# 01_Power_Suppy.net
KiCad netlist of a schematic drawn in Altium Designer
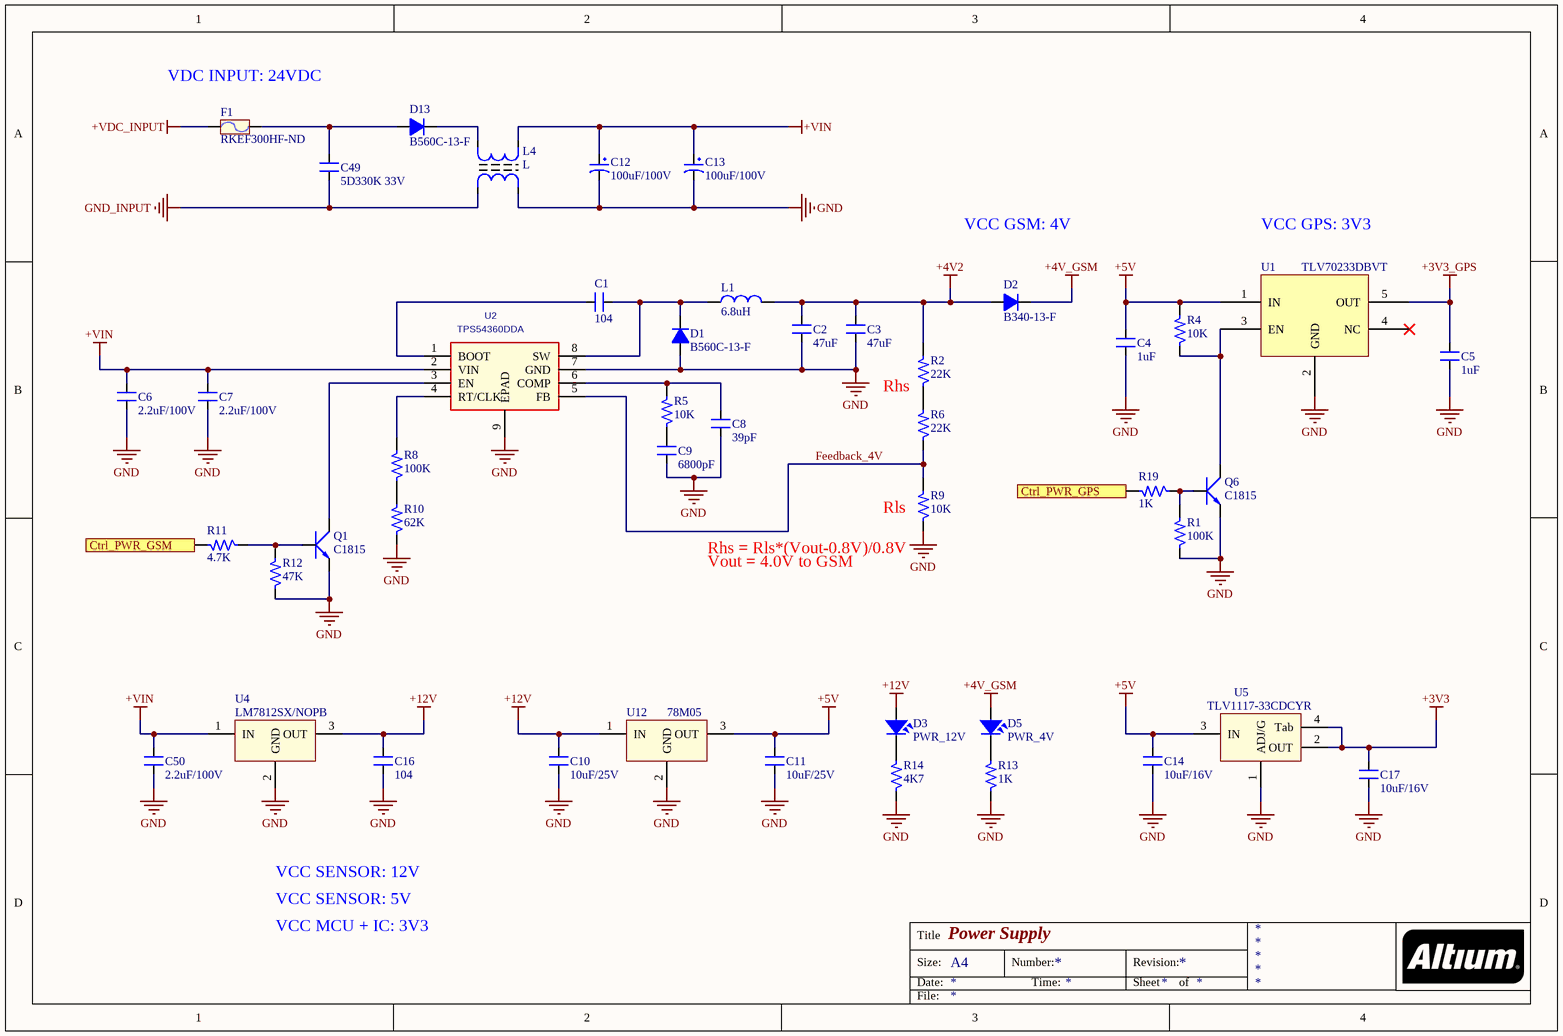
[diagram p0: [01] Power Suppy.SchDoc]

(export (version "E")
  (design (tool "Eeschema 10.0.6"))
  (components
    (comp (ref "C1")
      (value "104")
      (footprint "C0603 SMT")
      (description "Cap SMD")
      (libsource (lib "GPS_Traking_V1_1") (part "CM"))
    )
    (comp (ref "C2")
      (value "47uF")
      (footprint "SM-1210")
      (description "CAP CER 47UF 10V X5R 1210")
      (libsource (lib "GPS_Traking_V1_1") (part "CM"))
    )
    (comp (ref "C3")
      (value "47uF")
      (footprint "SM-1210")
      (description "CAP CER 47UF 10V X5R 1210 1276-3380-2-ND")
      (libsource (lib "GPS_Traking_V1_1") (part "CM"))
    )
    (comp (ref "C4")
      (value "1uF")
      (footprint "C0603 SMT")
      (description "Cap SMD")
      (libsource (lib "GPS_Traking_V1_1") (part "CM"))
    )
    (comp (ref "C5")
      (value "1uF")
      (footprint "C0603 SMT")
      (description "Cap SMD")
      (libsource (lib "GPS_Traking_V1_1") (part "CM"))
    )
    (comp (ref "C6")
      (value "2.2uF/100V")
      (footprint "SM-1210")
      (description "CAP CER 2.2UF 100V X7R 1210  445-4498-2-ND")
      (libsource (lib "GPS_Traking_V1_1") (part "CM"))
    )
    (comp (ref "C7")
      (value "2.2uF/100V")
      (footprint "SM-1210")
      (description "CAP CER 2.2UF 100V X7R 1210  445-4498-2-ND")
      (libsource (lib "GPS_Traking_V1_1") (part "CM"))
    )
    (comp (ref "C8")
      (value "39pF")
      (footprint "C0603 SMT")
      (description "Cap SMD")
      (libsource (lib "GPS_Traking_V1_1") (part "CM"))
    )
    (comp (ref "C9")
      (value "6800pF")
      (footprint "C0603 SMT")
      (description "Cap SMD")
      (libsource (lib "GPS_Traking_V1_1") (part "CM"))
    )
    (comp (ref "C10")
      (value "10uF/25V")
      (footprint "C0603 SMT")
      (description "Cap SMD")
      (libsource (lib "GPS_Traking_V1_1") (part "CM"))
    )
    (comp (ref "C11")
      (value "10uF/25V")
      (footprint "C0603 SMT")
      (description "Cap SMD")
      (libsource (lib "GPS_Traking_V1_1") (part "CM"))
    )
    (comp (ref "C12")
      (value "100uF/100V")
      (footprint "CP1.5/3.4")
      (description "Cap 1000uF/16V - 220uF/50V")
      (libsource (lib "GPS_Traking_V1_1") (part "CP4"))
    )
    (comp (ref "C13")
      (value "100uF/100V")
      (footprint "CP1.5/3.4")
      (description "Cap 1000uF/16V - 220uF/50V")
      (libsource (lib "GPS_Traking_V1_1") (part "CP4"))
    )
    (comp (ref "C14")
      (value "10uF/16V")
      (footprint "C0603 SMT")
      (description "Cap SMD")
      (libsource (lib "GPS_Traking_V1_1") (part "CM"))
    )
    (comp (ref "C16")
      (value "104")
      (footprint "C0603 SMT")
      (description "Cap SMD")
      (libsource (lib "GPS_Traking_V1_1") (part "CM"))
    )
    (comp (ref "C17")
      (value "10uF/16V")
      (footprint "C0603 SMT")
      (description "Cap SMD")
      (libsource (lib "GPS_Traking_V1_1") (part "CM"))
    )
    (comp (ref "C49")
      (value "5D330K 33V")
      (footprint "CN2")
      (fields (field (name "DESIGNED BY") "VanDungEvn"))
      (libsource (lib "khapham") (part "CN"))
    )
    (comp (ref "C50")
      (value "2.2uF/100V")
      (footprint "SM-1210")
      (description "CAP CER 2.2UF 100V X7R 1210  445-4498-2-ND")
      (libsource (lib "GPS_Traking_V1_1") (part "CM"))
    )
    (comp (ref "D1")
      (value "B560C-13-F")
      (footprint "DO-214AB SMC")
      (description "DIODE SCHOTTKY 60V 5A SMC")
      (libsource (lib "GPS_Traking_V1_1") (part "D5A"))
    )
    (comp (ref "D2")
      (value "B340-13-F")
      (footprint "DO-214AB SMA")
      (description "DIODE SCHOTTKY 40V 3A SMC")
      (libsource (lib "GPS_Traking_V1_1") (part "D1A"))
    )
    (comp (ref "D3")
      (value "PWR_12V")
      (footprint "Led_0603_Yellow")
      (description "LED Single colour Green and Red")
      (libsource (lib "GPS_Traking_V1_1") (part "LED"))
    )
    (comp (ref "D5")
      (value "PWR_4V")
      (footprint "Led_0603_Green")
      (description "LED Single colour Green and Red")
      (libsource (lib "GPS_Traking_V1_1") (part "LED"))
    )
    (comp (ref "D13")
      (value "B560C-13-F")
      (footprint "DO-214AB SMC")
      (description "DIODE SCHOTTKY 60V 5A SMC")
      (libsource (lib "GPS_Traking_V1_1") (part "D5A"))
    )
    (comp (ref "F1")
      (value "RKEF300HF-ND")
      (footprint "FUSE2")
      (description "PTC RESET FUSE 60V 3A RADIAL")
      (fields (field (name "DESIGNED BY") "VanDungEvn"))
      (libsource (lib "khapham") (part "Fuse"))
    )
    (comp (ref "L1")
      (value "6.8uH")
      (footprint "L01 SMD 12*12*6")
      (description "FIXED IND 6.2UH 5.7A 22.4 MOHM")
      (libsource (lib "GPS_Traking_V1_1") (part "L1"))
    )
    (comp (ref "L4")
      (value "L")
      (footprint "L2 UF9.8")
      (description "Inductor")
      (fields (field (name "DESIGNED BY") "VanDungEvn"))
      (libsource (lib "GPS_Traking_V1_1") (part "L2x220"))
    )
    (comp (ref "Q1")
      (value "C1815")
      (footprint "SOT23B")
      (description "NPN 600mW, ECB")
      (libsource (lib "GPS_Traking_V1_1") (part "C1815"))
    )
    (comp (ref "Q6")
      (value "C1815")
      (footprint "SOT23B")
      (description "NPN 600mW, ECB")
      (libsource (lib "GPS_Traking_V1_1") (part "C1815"))
    )
    (comp (ref "R1")
      (value "100K")
      (footprint "R0603 -SMT")
      (description "Resistor SMD")
      (libsource (lib "GPS_Traking_V1_1") (part "RM"))
    )
    (comp (ref "R2")
      (value "22K")
      (footprint "R0603 -SMT")
      (description "Resistor SMD")
      (libsource (lib "GPS_Traking_V1_1") (part "RM"))
    )
    (comp (ref "R4")
      (value "10K")
      (footprint "R0603 -SMT")
      (description "Resistor SMD")
      (libsource (lib "GPS_Traking_V1_1") (part "RM"))
    )
    (comp (ref "R5")
      (value "10K")
      (footprint "R0603 -SMT")
      (description "Resistor SMD")
      (libsource (lib "GPS_Traking_V1_1") (part "RM"))
    )
    (comp (ref "R6")
      (value "22K")
      (footprint "R0603 -SMT")
      (description "Resistor SMD")
      (libsource (lib "GPS_Traking_V1_1") (part "RM"))
    )
    (comp (ref "R8")
      (value "100K")
      (footprint "R0603 -SMT")
      (description "Resistor SMD")
      (libsource (lib "GPS_Traking_V1_1") (part "RM"))
    )
    (comp (ref "R9")
      (value "10K")
      (footprint "R0603 -SMT")
      (description "Resistor SMD")
      (libsource (lib "GPS_Traking_V1_1") (part "RM"))
    )
    (comp (ref "R10")
      (value "62K")
      (footprint "R0603 -SMT")
      (description "Resistor SMD")
      (libsource (lib "GPS_Traking_V1_1") (part "RM"))
    )
    (comp (ref "R11")
      (value "4.7K")
      (footprint "R0603 -SMT")
      (description "Resistor SMD")
      (libsource (lib "GPS_Traking_V1_1") (part "RM"))
    )
    (comp (ref "R12")
      (value "47K")
      (footprint "R0603 -SMT")
      (description "Resistor SMD")
      (libsource (lib "GPS_Traking_V1_1") (part "RM"))
    )
    (comp (ref "R13")
      (value "1K")
      (footprint "R0603 -SMT")
      (description "Resistor SMD")
      (libsource (lib "GPS_Traking_V1_1") (part "RM"))
    )
    (comp (ref "R14")
      (value "4K7")
      (footprint "R0603 -SMT")
      (description "Resistor SMD")
      (libsource (lib "GPS_Traking_V1_1") (part "RM"))
    )
    (comp (ref "R19")
      (value "1K")
      (footprint "R0603 -SMT")
      (description "Resistor SMD")
      (libsource (lib "GPS_Traking_V1_1") (part "RM"))
    )
    (comp (ref "U1")
      (value "TLV70233DBVT")
      (footprint "TLV70233_3.3V")
      (libsource (lib "GPS_Traking_V1_1") (part "TLV70233_3.3V"))
    )
    (comp (ref "U2")
      (value "TPS54360DDA")
      (footprint "DDA8_3P1X2P4-M")
      (description "REG BUCK SPLIT RAIL 8SOPWRPAD")
      (libsource (lib "GPS_Traking_V1_1") (part "TPS54360DDA"))
    )
    (comp (ref "U4")
      (value "LM7812SX/NOPB")
      (footprint "TO-263-4")
      (libsource (lib "GPS_Traking_V1_1") (part "LM78xx"))
    )
    (comp (ref "U5")
      (value "TLV1117-33CDCYR")
      (footprint "SOT223-4N")
      (description "3v3")
      (libsource (lib "GPS_Traking_V1_1") (part "LM1117"))
    )
    (comp (ref "U12")
      (value "78M05")
      (footprint "TO252-3L")
      (description "On ap +, from + 5 to + 24VDC")
      (libsource (lib "GPS_Traking_V1_1") (part "LM78xx"))
    )
  )
  (nets
    (net (code "1") (name "+3V3") (class "Default")
      (node (ref "C17") (pin "2") (pinfunction "2_2") (pintype "passive"))
      (node (ref "U5") (pin "2") (pinfunction "OUT_2") (pintype "passive"))
      (node (ref "U5") (pin "4") (pinfunction "Tab_4") (pintype "passive"))
    )
    (net (code "2") (name "+3V3_GPS") (class "Default")
      (node (ref "C5") (pin "2") (pinfunction "2_2") (pintype "passive"))
      (node (ref "U1") (pin "5") (pinfunction "OUT_5") (pintype "passive"))
    )
    (net (code "3") (name "+4V2") (class "Default")
      (node (ref "C2") (pin "2") (pinfunction "2_2") (pintype "passive"))
      (node (ref "C3") (pin "2") (pinfunction "2_2") (pintype "passive"))
      (node (ref "D2") (pin "1") (pinfunction "A_1") (pintype "passive"))
      (node (ref "L1") (pin "2") (pinfunction "2_2") (pintype "passive"))
      (node (ref "R2") (pin "2") (pinfunction "2_2") (pintype "passive"))
    )
    (net (code "4") (name "+4V_GSM") (class "Default")
      (node (ref "D2") (pin "2") (pinfunction "K_2") (pintype "passive"))
      (node (ref "D5") (pin "1") (pinfunction "1_1") (pintype "passive"))
    )
    (net (code "5") (name "+5V") (class "Default")
      (node (ref "C11") (pin "2") (pinfunction "2_2") (pintype "passive"))
      (node (ref "C14") (pin "2") (pinfunction "2_2") (pintype "passive"))
      (node (ref "C4") (pin "2") (pinfunction "2_2") (pintype "passive"))
      (node (ref "R4") (pin "2") (pinfunction "2_2") (pintype "passive"))
      (node (ref "U1") (pin "1") (pinfunction "IN_1") (pintype "passive"))
      (node (ref "U12") (pin "3") (pinfunction "OUT_3") (pintype "passive"))
      (node (ref "U5") (pin "3") (pinfunction "IN_3") (pintype "passive"))
    )
    (net (code "6") (name "+12V") (class "Default")
      (node (ref "C10") (pin "2") (pinfunction "2_2") (pintype "passive"))
      (node (ref "C16") (pin "2") (pinfunction "2_2") (pintype "passive"))
      (node (ref "D3") (pin "1") (pinfunction "1_1") (pintype "passive"))
      (node (ref "U12") (pin "1") (pinfunction "IN_1") (pintype "passive"))
      (node (ref "U4") (pin "3") (pinfunction "OUT_3") (pintype "passive"))
    )
    (net (code "7") (name "+VDC_INPUT") (class "Default")
      (node (ref "F1") (pin "1") (pinfunction "1_1") (pintype "passive"))
    )
    (net (code "8") (name "+VIN") (class "Default")
      (node (ref "C12") (pin "1") (pinfunction "1_1") (pintype "passive"))
      (node (ref "C13") (pin "1") (pinfunction "1_1") (pintype "passive"))
      (node (ref "C50") (pin "2") (pinfunction "2_2") (pintype "passive"))
      (node (ref "C6") (pin "2") (pinfunction "2_2") (pintype "passive"))
      (node (ref "C7") (pin "2") (pinfunction "2_2") (pintype "passive"))
      (node (ref "L4") (pin "3") (pinfunction "3_3") (pintype "passive"))
      (node (ref "U2") (pin "2") (pinfunction "VIN_2") (pintype "passive"))
      (node (ref "U4") (pin "1") (pinfunction "IN_1") (pintype "passive"))
    )
    (net (code "9") (name "/Ctrl_PWR_GPS") (class "Default")
      (node (ref "R19") (pin "2") (pinfunction "2_2") (pintype "passive"))
    )
    (net (code "10") (name "/Ctrl_PWR_GSM") (class "Default")
      (node (ref "R11") (pin "2") (pinfunction "2_2") (pintype "passive"))
    )
    (net (code "11") (name "/Feedback_4V") (class "Default")
      (node (ref "R6") (pin "1") (pinfunction "1_1") (pintype "passive"))
      (node (ref "R9") (pin "2") (pinfunction "2_2") (pintype "passive"))
      (node (ref "U2") (pin "5") (pinfunction "FB_5") (pintype "passive"))
    )
    (net (code "12") (name "GND") (class "Default")
      (node (ref "C10") (pin "1") (pinfunction "1_1") (pintype "passive"))
      (node (ref "C11") (pin "1") (pinfunction "1_1") (pintype "passive"))
      (node (ref "C12") (pin "2") (pinfunction "2_2") (pintype "passive"))
      (node (ref "C13") (pin "2") (pinfunction "2_2") (pintype "passive"))
      (node (ref "C14") (pin "1") (pinfunction "1_1") (pintype "passive"))
      (node (ref "C16") (pin "1") (pinfunction "1_1") (pintype "passive"))
      (node (ref "C17") (pin "1") (pinfunction "1_1") (pintype "passive"))
      (node (ref "C2") (pin "1") (pinfunction "1_1") (pintype "passive"))
      (node (ref "C3") (pin "1") (pinfunction "1_1") (pintype "passive"))
      (node (ref "C4") (pin "1") (pinfunction "1_1") (pintype "passive"))
      (node (ref "C5") (pin "1") (pinfunction "1_1") (pintype "passive"))
      (node (ref "C50") (pin "1") (pinfunction "1_1") (pintype "passive"))
      (node (ref "C6") (pin "1") (pinfunction "1_1") (pintype "passive"))
      (node (ref "C7") (pin "1") (pinfunction "1_1") (pintype "passive"))
      (node (ref "C8") (pin "1") (pinfunction "1_1") (pintype "passive"))
      (node (ref "C9") (pin "1") (pinfunction "1_1") (pintype "passive"))
      (node (ref "D1") (pin "1") (pinfunction "A_1") (pintype "passive"))
      (node (ref "L4") (pin "2") (pinfunction "2_2") (pintype "passive"))
      (node (ref "Q1") (pin "1") (pinfunction "E_1") (pintype "passive"))
      (node (ref "Q6") (pin "1") (pinfunction "E_1") (pintype "passive"))
      (node (ref "R1") (pin "1") (pinfunction "1_1") (pintype "passive"))
      (node (ref "R10") (pin "1") (pinfunction "1_1") (pintype "passive"))
      (node (ref "R12") (pin "1") (pinfunction "1_1") (pintype "passive"))
      (node (ref "R13") (pin "1") (pinfunction "1_1") (pintype "passive"))
      (node (ref "R14") (pin "1") (pinfunction "1_1") (pintype "passive"))
      (node (ref "R9") (pin "1") (pinfunction "1_1") (pintype "passive"))
      (node (ref "U1") (pin "2") (pinfunction "GND_2") (pintype "power_in"))
      (node (ref "U12") (pin "2") (pinfunction "GND_2") (pintype "passive"))
      (node (ref "U2") (pin "7") (pinfunction "GND_7") (pintype "passive"))
      (node (ref "U2") (pin "9") (pinfunction "EPAD_9") (pintype "passive"))
      (node (ref "U4") (pin "2") (pinfunction "GND_2") (pintype "passive"))
      (node (ref "U5") (pin "1") (pinfunction "ADJ/G_1") (pintype "passive"))
    )
    (net (code "13") (name "GND_INPUT") (class "Default")
      (node (ref "C49") (pin "1") (pinfunction "1_1") (pintype "passive"))
      (node (ref "L4") (pin "1") (pinfunction "1_1") (pintype "passive"))
    )
    (net (code "14") (name "Net-(C9-Pad2)") (class "Default")
      (node (ref "C9") (pin "2") (pinfunction "2_2") (pintype "passive"))
      (node (ref "R5") (pin "1") (pinfunction "1_1") (pintype "passive"))
    )
    (net (code "15") (name "Net-(D1-K)") (class "Default")
      (node (ref "C1") (pin "2") (pinfunction "2_2") (pintype "passive"))
      (node (ref "D1") (pin "2") (pinfunction "K_2") (pintype "passive"))
      (node (ref "L1") (pin "1") (pinfunction "1_1") (pintype "passive"))
      (node (ref "U2") (pin "8") (pinfunction "SW_8") (pintype "passive"))
    )
    (net (code "16") (name "Net-(D3-Pad2)") (class "Default")
      (node (ref "D3") (pin "2") (pinfunction "2_2") (pintype "passive"))
      (node (ref "R14") (pin "2") (pinfunction "2_2") (pintype "passive"))
    )
    (net (code "17") (name "Net-(D5-Pad2)") (class "Default")
      (node (ref "D5") (pin "2") (pinfunction "2_2") (pintype "passive"))
      (node (ref "R13") (pin "2") (pinfunction "2_2") (pintype "passive"))
    )
    (net (code "18") (name "Net-(D13-A)") (class "Default")
      (node (ref "C49") (pin "2") (pinfunction "2_2") (pintype "passive"))
      (node (ref "D13") (pin "1") (pinfunction "A_1") (pintype "passive"))
      (node (ref "F1") (pin "2") (pinfunction "2_2") (pintype "passive"))
    )
    (net (code "19") (name "Net-(D13-K)") (class "Default")
      (node (ref "D13") (pin "2") (pinfunction "K_2") (pintype "passive"))
      (node (ref "L4") (pin "4") (pinfunction "4_4") (pintype "passive"))
    )
    (net (code "20") (name "Net-(Q1-B)") (class "Default")
      (node (ref "Q1") (pin "3") (pinfunction "B_3") (pintype "passive"))
      (node (ref "R11") (pin "1") (pinfunction "1_1") (pintype "passive"))
      (node (ref "R12") (pin "2") (pinfunction "2_2") (pintype "passive"))
    )
    (net (code "21") (name "Net-(Q1-C)") (class "Default")
      (node (ref "Q1") (pin "2") (pinfunction "C_2") (pintype "passive"))
      (node (ref "U2") (pin "3") (pinfunction "EN_3") (pintype "passive"))
    )
    (net (code "22") (name "Net-(Q6-B)") (class "Default")
      (node (ref "Q6") (pin "3") (pinfunction "B_3") (pintype "passive"))
      (node (ref "R1") (pin "2") (pinfunction "2_2") (pintype "passive"))
      (node (ref "R19") (pin "1") (pinfunction "1_1") (pintype "passive"))
    )
    (net (code "23") (name "Net-(Q6-C)") (class "Default")
      (node (ref "Q6") (pin "2") (pinfunction "C_2") (pintype "passive"))
      (node (ref "R4") (pin "1") (pinfunction "1_1") (pintype "passive"))
      (node (ref "U1") (pin "3") (pinfunction "EN_3") (pintype "passive"))
    )
    (net (code "24") (name "Net-(R2-Pad1)") (class "Default")
      (node (ref "R2") (pin "1") (pinfunction "1_1") (pintype "passive"))
      (node (ref "R6") (pin "2") (pinfunction "2_2") (pintype "passive"))
    )
    (net (code "25") (name "Net-(R10-Pad2)") (class "Default")
      (node (ref "R10") (pin "2") (pinfunction "2_2") (pintype "passive"))
      (node (ref "R8") (pin "1") (pinfunction "1_1") (pintype "passive"))
    )
    (net (code "26") (name "Net-(U2-BOOT)") (class "Default")
      (node (ref "C1") (pin "1") (pinfunction "1_1") (pintype "passive"))
      (node (ref "U2") (pin "1") (pinfunction "BOOT_1") (pintype "passive"))
    )
    (net (code "27") (name "Net-(U2-COMP)") (class "Default")
      (node (ref "C8") (pin "2") (pinfunction "2_2") (pintype "passive"))
      (node (ref "R5") (pin "2") (pinfunction "2_2") (pintype "passive"))
      (node (ref "U2") (pin "6") (pinfunction "COMP_6") (pintype "passive"))
    )
    (net (code "28") (name "Net-(U2-RT{slash}CLK)") (class "Default")
      (node (ref "R8") (pin "2") (pinfunction "2_2") (pintype "passive"))
      (node (ref "U2") (pin "4") (pinfunction "RT/CLK_4") (pintype "passive"))
    )
    (net (code "29") (name "unconnected-(U1-NC-Pad4)") (class "Default")
      (node (ref "U1") (pin "4") (pinfunction "NC_4") (pintype "passive+no_connect"))
    )
  )
)
